# Main.net
KiCad netlist of a schematic drawn in Altium Designer
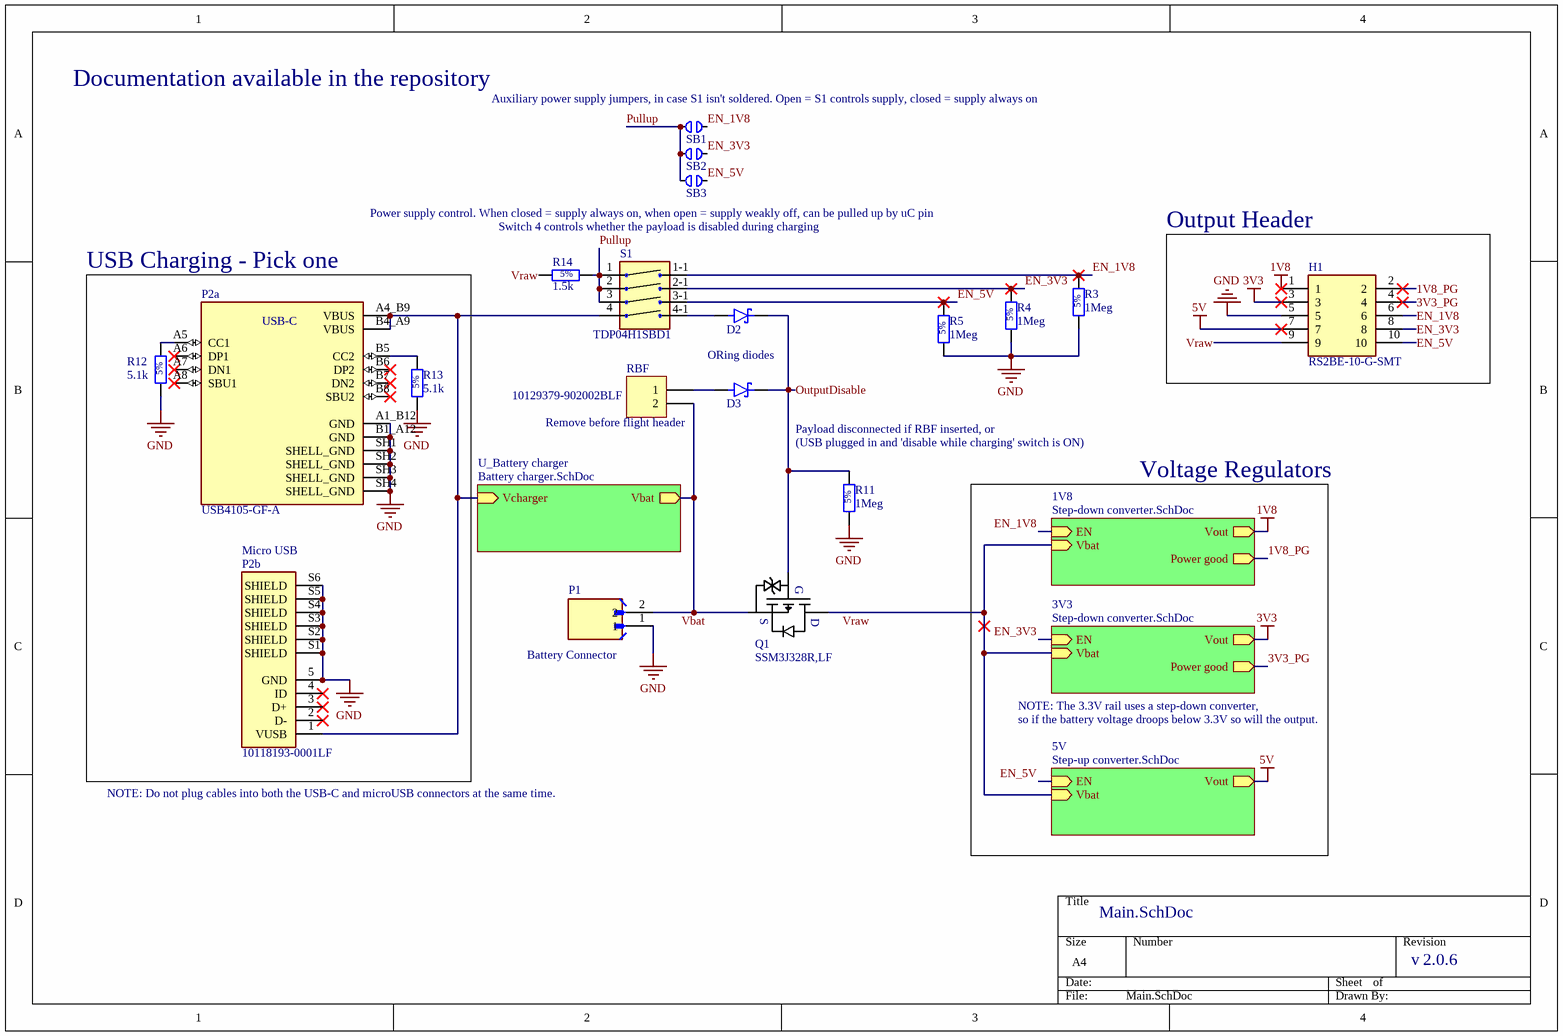
[diagram p0: Main.SchDoc]

(export (version "E")
  (design (tool "Eeschema 10.0.6"))
  (components
    (comp (ref "D2")
      (value "SS0520_R1_00001")
      (footprint "APSS Prototype Parts:SOD123-1.35mm-N")
      (description "Diode - Low Forward Voltage, Schottky, 385 mV @ 500 mA, 75 µA Reverse @ 10 V, SOD-123")
      (fields (field (name "APSS STANDARD PART") "APSS Standard"))
      (libsource (lib "APSS Prototype Parts") (part "SS0520_R1_00001"))
    )
    (comp (ref "D3")
      (value "SS0520_R1_00001")
      (footprint "APSS Prototype Parts:SOD123-1.35mm-N")
      (description "Diode - Low Forward Voltage, Schottky, 385 mV @ 500 mA, 75 µA Reverse @ 10 V, SOD-123")
      (fields (field (name "APSS STANDARD PART") "APSS Standard"))
      (libsource (lib "APSS Prototype Parts") (part "SS0520_R1_00001"))
    )
    (comp (ref "H1")
      (value "RS2BE-10-G-SMT")
      (footprint "RS2BE10GSMT")
      (description "Receptacle Strip 10P 2.54mm Pitch SMT")
      (libsource (lib "RS2BE-10-G-SMT") (part "RS2BE-10-G-SMT"))
    )
    (comp (ref "P1")
      (value "B2B-PH-K-S(LF)(SN)")
      (footprint "JST_B2B-PH-K-S(LF)(SN)")
      (description "Connector Header Through Hole 2 position 0.079 (2.00mm)")
      (fields (field (name "MF PART NO.") "B2B-PH-K-S (LF)(SN)"))
      (libsource (lib "B2B-PH-K-S_LF__SN_") (part "B2B-PH-K-S(LF)(SN)"))
    )
    (comp (ref "P2a")
      (value "USB4105-GF-A")
      (footprint "GCT_USB4105-GF-A")
      (libsource (lib "USB4105-GF-A") (part "USB4105-GF-A"))
    )
    (comp (ref "P2b")
      (value "10118193-0001LF")
      (footprint "AMPHENOL_10118193-0001LF")
      (description "Micro USB 2.0, Input Output Connectors, B TYPE RECEPTACLE")
      (fields (field (name "MF") "Amphenol ICC"))
      (libsource (lib "10118193-0001LF") (part "10118193-0001LF"))
    )
    (comp (ref "Q1")
      (value "SSM3J328R,LF")
      (footprint "APSS Prototype Parts:SOT23F-3-0.8mm")
      (description "Transistor - MOSFET, P-Channel SSM3J328R,LF")
      (fields (field (name "POWER") "1W") (field (name "APSS STANDARD PART") "APSS Standard"))
      (libsource (lib "APSS Prototype Parts") (part "SSM3J328R,LF"))
    )
    (comp (ref "R3")
      (value "1Meg")
      (footprint "APSS Flight Parts:Resistor_0805_2012M-50N")
      (fields
        (field (name "TOLERANCE") "5%")
        (field (name "POWER") "1/8W")
        (field (name "MF PART NO.") "RMCF0805JT1M00")
      )
      (libsource (lib "APSS Prototype Parts") (part "RMCF0805JT Series"))
    )
    (comp (ref "R4")
      (value "1Meg")
      (footprint "APSS Flight Parts:Resistor_0805_2012M-50N")
      (fields
        (field (name "TOLERANCE") "5%")
        (field (name "POWER") "1/8W")
        (field (name "MF PART NO.") "RMCF0805JT1M00")
      )
      (libsource (lib "APSS Prototype Parts") (part "RMCF0805JT Series"))
    )
    (comp (ref "R5")
      (value "1Meg")
      (footprint "APSS Flight Parts:Resistor_0805_2012M-50N")
      (fields
        (field (name "TOLERANCE") "5%")
        (field (name "POWER") "1/8W")
        (field (name "MF PART NO.") "RMCF0805JT1M00")
      )
      (libsource (lib "APSS Prototype Parts") (part "RMCF0805JT Series"))
    )
    (comp (ref "R11")
      (value "1Meg")
      (footprint "APSS Flight Parts:Resistor_0805_2012M-50N")
      (fields
        (field (name "TOLERANCE") "5%")
        (field (name "POWER") "1/8W")
        (field (name "MF PART NO.") "RMCF0805JT1M00")
      )
      (libsource (lib "APSS Prototype Parts") (part "RMCF0805JT Series"))
    )
    (comp (ref "R12")
      (value "5.1k")
      (footprint "APSS Flight Parts:Resistor_0805_2012M-50N")
      (fields
        (field (name "TOLERANCE") "5%")
        (field (name "POWER") "1/8W")
        (field (name "MF PART NO.") "RMCF0805JT5K10")
      )
      (libsource (lib "APSS Prototype Parts") (part "RMCF0805JT Series"))
    )
    (comp (ref "R13")
      (value "5.1k")
      (footprint "APSS Flight Parts:Resistor_0805_2012M-50N")
      (fields
        (field (name "TOLERANCE") "5%")
        (field (name "POWER") "1/8W")
        (field (name "MF PART NO.") "RMCF0805JT5K10")
      )
      (libsource (lib "APSS Prototype Parts") (part "RMCF0805JT Series"))
    )
    (comp (ref "R14")
      (value "1.5k")
      (footprint "APSS Flight Parts:Resistor_0805_2012M-50N")
      (fields
        (field (name "TOLERANCE") "5%")
        (field (name "POWER") "1/8W")
        (field (name "MF PART NO.") "RMCF0805JT1K50")
      )
      (libsource (lib "") (part "RMCF0805JT Series_1"))
    )
    (comp (ref "RBF")
      (value "~")
      (footprint "ECE-600102STTH-RA")
      (description "Short Before Flight")
      (libsource (lib "EceParts") (part "Header 2"))
    )
    (comp (ref "S1")
      (value "TDP04H1SBD1")
      (footprint "TDP04H1SBD1")
      (description "Switch")
      (libsource (lib "APSS Generic Components") (part "TDP04H1SBD1"))
    )
    (comp (ref "SB1")
      (value "Solder Jumper Normally Open 0201")
      (footprint "Solder Bridge Open 0201")
      (libsource (lib "APSS Generic Components") (part "Solder Jumper Normally Open 0201"))
    )
    (comp (ref "SB2")
      (value "Solder Jumper Normally Open 0201")
      (footprint "Solder Bridge Open 0201")
      (libsource (lib "APSS Generic Components") (part "Solder Jumper Normally Open 0201"))
    )
    (comp (ref "SB3")
      (value "Solder Jumper Normally Open 0201")
      (footprint "Solder Bridge Open 0201")
      (libsource (lib "APSS Generic Components") (part "Solder Jumper Normally Open 0201"))
    )
  )
  (nets
    (net (code "1") (name "/1V8_PG") (class "Default")
      (node (ref "H1") (pin "2") (pinfunction "2_2") (pintype "passive"))
    )
    (net (code "2") (name "/3V3_PG") (class "Default")
      (node (ref "H1") (pin "4") (pinfunction "4_4") (pintype "passive"))
    )
    (net (code "3") (name "/EN_1V8") (class "Default")
      (node (ref "H1") (pin "6") (pinfunction "6_6") (pintype "passive"))
      (node (ref "R3") (pin "2") (pinfunction "2_2") (pintype "passive"))
      (node (ref "S1") (pin "8") (pinfunction "1-1_8") (pintype "passive"))
      (node (ref "SB1") (pin "2") (pinfunction "2_2") (pintype "passive"))
    )
    (net (code "4") (name "/EN_3V3") (class "Default")
      (node (ref "H1") (pin "8") (pinfunction "8_8") (pintype "passive"))
      (node (ref "R4") (pin "2") (pinfunction "2_2") (pintype "passive"))
      (node (ref "S1") (pin "7") (pinfunction "2-1_7") (pintype "passive"))
      (node (ref "SB2") (pin "2") (pinfunction "2_2") (pintype "passive"))
    )
    (net (code "5") (name "/EN_5V") (class "Default")
      (node (ref "H1") (pin "10") (pinfunction "10_10") (pintype "passive"))
      (node (ref "R5") (pin "2") (pinfunction "2_2") (pintype "passive"))
      (node (ref "S1") (pin "6") (pinfunction "3-1_6") (pintype "passive"))
      (node (ref "SB3") (pin "2") (pinfunction "2_2") (pintype "passive"))
    )
    (net (code "6") (name "/OutputDisable") (class "Default")
      (node (ref "D2") (pin "C") (pinfunction "C_C") (pintype "passive"))
      (node (ref "D3") (pin "C") (pinfunction "C_C") (pintype "passive"))
      (node (ref "Q1") (pin "1") (pinfunction "G_1") (pintype "passive"))
      (node (ref "R11") (pin "2") (pinfunction "2_2") (pintype "passive"))
    )
    (net (code "7") (name "/Pullup") (class "Default")
      (node (ref "R14") (pin "2") (pinfunction "2_2") (pintype "passive"))
      (node (ref "S1") (pin "1") (pintype "passive"))
      (node (ref "S1") (pin "2") (pintype "passive"))
      (node (ref "S1") (pin "3") (pintype "passive"))
      (node (ref "SB1") (pin "1") (pinfunction "1_1") (pintype "passive"))
      (node (ref "SB2") (pin "1") (pinfunction "1_1") (pintype "passive"))
      (node (ref "SB3") (pin "1") (pinfunction "1_1") (pintype "passive"))
    )
    (net (code "8") (name "/Vbat") (class "Default")
      (node (ref "P1") (pin "2") (pinfunction "2_2") (pintype "passive"))
      (node (ref "Q1") (pin "2") (pinfunction "S_2") (pintype "passive"))
      (node (ref "RBF") (pin "2") (pinfunction "2_2") (pintype "passive"))
    )
    (net (code "9") (name "/Vcharger") (class "Default")
      (node (ref "P2a") (pin "A4_B9") (pinfunction "VBUS_A4_B9") (pintype "power_in"))
      (node (ref "P2a") (pin "B4_A9") (pinfunction "VBUS_B4_A9") (pintype "power_in"))
      (node (ref "P2b") (pin "1") (pinfunction "VUSB_1") (pintype "passive"))
      (node (ref "S1") (pin "4") (pintype "passive"))
    )
    (net (code "10") (name "/Vraw") (class "Default")
      (node (ref "H1") (pin "9") (pinfunction "9_9") (pintype "passive"))
      (node (ref "Q1") (pin "3") (pinfunction "D_3") (pintype "passive"))
      (node (ref "R14") (pin "1") (pinfunction "1_1") (pintype "passive"))
    )
    (net (code "11") (name "1V8") (class "Default")
      (node (ref "H1") (pin "1") (pinfunction "1_1") (pintype "passive"))
    )
    (net (code "12") (name "3V3") (class "Default")
      (node (ref "H1") (pin "3") (pinfunction "3_3") (pintype "passive"))
    )
    (net (code "13") (name "5V") (class "Default")
      (node (ref "H1") (pin "7") (pinfunction "7_7") (pintype "passive"))
    )
    (net (code "14") (name "GND") (class "Default")
      (node (ref "H1") (pin "5") (pinfunction "5_5") (pintype "passive"))
      (node (ref "P1") (pin "1") (pinfunction "1_1") (pintype "passive"))
      (node (ref "P2a") (pin "A1_B12") (pinfunction "GND_A1_B12") (pintype "power_in"))
      (node (ref "P2a") (pin "B1_A12") (pinfunction "GND_B1_A12") (pintype "power_in"))
      (node (ref "P2a") (pin "SH1") (pinfunction "SHELL_GND_SH1") (pintype "power_in"))
      (node (ref "P2a") (pin "SH2") (pinfunction "SHELL_GND_SH2") (pintype "power_in"))
      (node (ref "P2a") (pin "SH3") (pinfunction "SHELL_GND_SH3") (pintype "power_in"))
      (node (ref "P2a") (pin "SH4") (pinfunction "SHELL_GND_SH4") (pintype "power_in"))
      (node (ref "P2b") (pin "5") (pinfunction "GND_5") (pintype "passive"))
      (node (ref "P2b") (pin "S1") (pinfunction "SHIELD_S1") (pintype "passive"))
      (node (ref "P2b") (pin "S2") (pinfunction "SHIELD_S2") (pintype "passive"))
      (node (ref "P2b") (pin "S3") (pinfunction "SHIELD_S3") (pintype "passive"))
      (node (ref "P2b") (pin "S4") (pinfunction "SHIELD_S4") (pintype "passive"))
      (node (ref "P2b") (pin "S5") (pinfunction "SHIELD_S5") (pintype "passive"))
      (node (ref "P2b") (pin "S6") (pinfunction "SHIELD_S6") (pintype "passive"))
      (node (ref "R11") (pin "1") (pinfunction "1_1") (pintype "passive"))
      (node (ref "R12") (pin "1") (pinfunction "1_1") (pintype "passive"))
      (node (ref "R13") (pin "1") (pinfunction "1_1") (pintype "passive"))
      (node (ref "R3") (pin "1") (pinfunction "1_1") (pintype "passive"))
      (node (ref "R4") (pin "1") (pinfunction "1_1") (pintype "passive"))
      (node (ref "R5") (pin "1") (pinfunction "1_1") (pintype "passive"))
    )
    (net (code "15") (name "Net-(D3-PadA)") (class "Default")
      (node (ref "D3") (pin "A") (pinfunction "A_A") (pintype "passive"))
      (node (ref "RBF") (pin "1") (pinfunction "1_1") (pintype "passive"))
    )
    (net (code "16") (name "Net-(P2a-CC1)") (class "Default")
      (node (ref "P2a") (pin "A5") (pinfunction "CC1_A5") (pintype "bidirectional"))
      (node (ref "R12") (pin "2") (pinfunction "2_2") (pintype "passive"))
    )
    (net (code "17") (name "Net-(P2a-CC2)") (class "Default")
      (node (ref "P2a") (pin "B5") (pinfunction "CC2_B5") (pintype "bidirectional"))
      (node (ref "R13") (pin "2") (pinfunction "2_2") (pintype "passive"))
    )
    (net (code "18") (name "Net-(S1-4-1)") (class "Default")
      (node (ref "D2") (pin "A") (pinfunction "A_A") (pintype "passive"))
      (node (ref "S1") (pin "5") (pinfunction "4-1_5") (pintype "passive"))
    )
    (net (code "19") (name "unconnected-(P2a-DN1-PadA7)") (class "Default")
      (node (ref "P2a") (pin "A7") (pinfunction "DN1_A7") (pintype "bidirectional+no_connect"))
    )
    (net (code "20") (name "unconnected-(P2a-DN2-PadB7)") (class "Default")
      (node (ref "P2a") (pin "B7") (pinfunction "DN2_B7") (pintype "bidirectional+no_connect"))
    )
    (net (code "21") (name "unconnected-(P2a-DP1-PadA6)") (class "Default")
      (node (ref "P2a") (pin "A6") (pinfunction "DP1_A6") (pintype "bidirectional+no_connect"))
    )
    (net (code "22") (name "unconnected-(P2a-DP2-PadB6)") (class "Default")
      (node (ref "P2a") (pin "B6") (pinfunction "DP2_B6") (pintype "bidirectional+no_connect"))
    )
    (net (code "23") (name "unconnected-(P2a-SBU1-PadA8)") (class "Default")
      (node (ref "P2a") (pin "A8") (pinfunction "SBU1_A8") (pintype "bidirectional+no_connect"))
    )
    (net (code "24") (name "unconnected-(P2a-SBU2-PadB8)") (class "Default")
      (node (ref "P2a") (pin "B8") (pinfunction "SBU2_B8") (pintype "bidirectional+no_connect"))
    )
    (net (code "25") (name "unconnected-(P2b-D+-Pad3)") (class "Default")
      (node (ref "P2b") (pin "3") (pinfunction "D+_3") (pintype "passive+no_connect"))
    )
    (net (code "26") (name "unconnected-(P2b-D--Pad2)") (class "Default")
      (node (ref "P2b") (pin "2") (pinfunction "D-_2") (pintype "passive+no_connect"))
    )
    (net (code "27") (name "unconnected-(P2b-ID-Pad4)") (class "Default")
      (node (ref "P2b") (pin "4") (pinfunction "ID_4") (pintype "passive+no_connect"))
    )
  )
)
